# v001.net
KiCad netlist of a schematic drawn in EAGLE
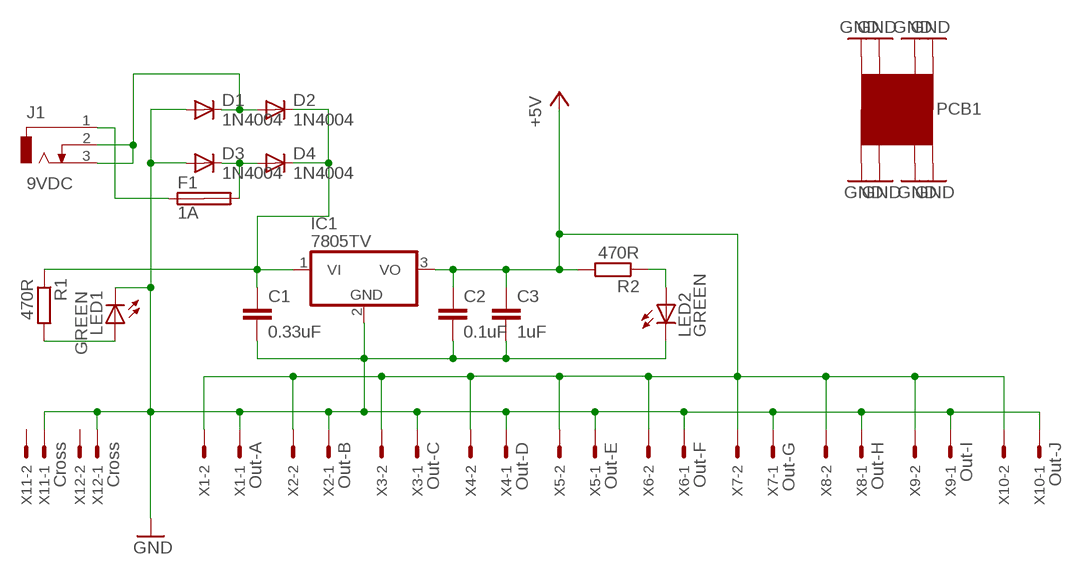
[diagram p0: schematic, sheet 1]

(export (version "E")
  (design (tool "Eeschema 10.0.6"))
  (components
    (comp (ref "C1")
      (value "0.33uF")
      (footprint "eagle-import:C050-030X075")
      (libsource (lib "eagle-import") (part "C-EU050-030X075"))
    )
    (comp (ref "C2")
      (value "0.1uF")
      (footprint "eagle-import:C050-024X044")
      (libsource (lib "eagle-import") (part "C-EU050-024X044"))
    )
    (comp (ref "C3")
      (value "1uF")
      (footprint "eagle-import:C050-045X075")
      (libsource (lib "eagle-import") (part "C-EU050-045X075"))
    )
    (comp (ref "D1")
      (value "1N4004")
      (footprint "eagle-import:DO35-7")
      (libsource (lib "eagle-import") (part "1N4148DO35-7"))
    )
    (comp (ref "D2")
      (value "1N4004")
      (footprint "eagle-import:DO35-7")
      (libsource (lib "eagle-import") (part "1N4148DO35-7"))
    )
    (comp (ref "D3")
      (value "1N4004")
      (footprint "eagle-import:DO35-7")
      (libsource (lib "eagle-import") (part "1N4148DO35-7"))
    )
    (comp (ref "D4")
      (value "1N4004")
      (footprint "eagle-import:DO35-7")
      (libsource (lib "eagle-import") (part "1N4148DO35-7"))
    )
    (comp (ref "F1")
      (value "1A")
      (footprint "eagle-import:SHK20L")
      (libsource (lib "eagle-import") (part "SHK20L"))
    )
    (comp (ref "IC1")
      (value "7805TV")
      (footprint "eagle-import:TO220V")
      (libsource (lib "eagle-import") (part "78TV05"))
    )
    (comp (ref "J1")
      (value "9VDC")
      (footprint "eagle-import:DCJ0202")
      (libsource (lib "eagle-import") (part "DCJ0202"))
    )
    (comp (ref "LED1")
      (value "GREEN")
      (footprint "eagle-import:LED3MM")
      (libsource (lib "eagle-import") (part "LED3MM"))
    )
    (comp (ref "LED2")
      (value "GREEN")
      (footprint "eagle-import:LED3MM")
      (libsource (lib "eagle-import") (part "LED3MM"))
    )
    (comp (ref "PCB1")
      (value "PCB05X05")
      (footprint "eagle-import:PCB_05X05")
      (libsource (lib "eagle-import") (part "PCB05X05"))
    )
    (comp (ref "R1")
      (value "470R")
      (footprint "eagle-import:0204_7")
      (libsource (lib "eagle-import") (part "R-EU_0204/7"))
    )
    (comp (ref "R2")
      (value "470R")
      (footprint "eagle-import:0204_7")
      (libsource (lib "eagle-import") (part "R-EU_0204/7"))
    )
    (comp (ref "X1")
      (value "Out-A")
      (footprint "eagle-import:6410-02")
      (libsource (lib "eagle-import") (part "22-?-0227-2021"))
    )
    (comp (ref "X2")
      (value "Out-B")
      (footprint "eagle-import:6410-02")
      (libsource (lib "eagle-import") (part "22-?-0227-2021"))
    )
    (comp (ref "X3")
      (value "Out-C")
      (footprint "eagle-import:6410-02")
      (libsource (lib "eagle-import") (part "22-?-0227-2021"))
    )
    (comp (ref "X4")
      (value "Out-D")
      (footprint "eagle-import:6410-02")
      (libsource (lib "eagle-import") (part "22-?-0227-2021"))
    )
    (comp (ref "X5")
      (value "Out-E")
      (footprint "eagle-import:6410-02")
      (libsource (lib "eagle-import") (part "22-?-0227-2021"))
    )
    (comp (ref "X6")
      (value "Out-F")
      (footprint "eagle-import:6410-02")
      (libsource (lib "eagle-import") (part "22-?-0227-2021"))
    )
    (comp (ref "X7")
      (value "Out-G")
      (footprint "eagle-import:6410-02")
      (libsource (lib "eagle-import") (part "22-?-0227-2021"))
    )
    (comp (ref "X8")
      (value "Out-H")
      (footprint "eagle-import:6410-02")
      (libsource (lib "eagle-import") (part "22-?-0227-2021"))
    )
    (comp (ref "X9")
      (value "Out-I")
      (footprint "eagle-import:6410-02")
      (libsource (lib "eagle-import") (part "22-?-0227-2021"))
    )
    (comp (ref "X10")
      (value "Out-J")
      (footprint "eagle-import:6410-02")
      (libsource (lib "eagle-import") (part "22-?-0227-2021"))
    )
    (comp (ref "X11")
      (value "Cross")
      (footprint "eagle-import:6410-02")
      (libsource (lib "eagle-import") (part "22-?-0227-2021"))
    )
    (comp (ref "X12")
      (value "Cross")
      (footprint "eagle-import:6410-02")
      (libsource (lib "eagle-import") (part "22-?-0227-2021"))
    )
  )
  (nets
    (net (code "1") (name "+5V") (class "Default")
      (node (ref "C2") (pin "1") (pinfunction "1_1") (pintype "passive"))
      (node (ref "C3") (pin "1") (pinfunction "1_1") (pintype "passive"))
      (node (ref "IC1") (pin "3") (pinfunction "VO_3") (pintype "passive"))
      (node (ref "R2") (pin "2") (pinfunction "2_2") (pintype "passive"))
      (node (ref "X1") (pin "2") (pinfunction "S_2") (pintype "passive"))
      (node (ref "X10") (pin "2") (pinfunction "S_2") (pintype "passive"))
      (node (ref "X2") (pin "2") (pinfunction "S_2") (pintype "passive"))
      (node (ref "X3") (pin "2") (pinfunction "S_2") (pintype "passive"))
      (node (ref "X4") (pin "2") (pinfunction "S_2") (pintype "passive"))
      (node (ref "X5") (pin "2") (pinfunction "S_2") (pintype "passive"))
      (node (ref "X6") (pin "2") (pinfunction "S_2") (pintype "passive"))
      (node (ref "X7") (pin "2") (pinfunction "S_2") (pintype "passive"))
      (node (ref "X8") (pin "2") (pinfunction "S_2") (pintype "passive"))
      (node (ref "X9") (pin "2") (pinfunction "S_2") (pintype "passive"))
    )
    (net (code "2") (name "GND") (class "Default")
      (node (ref "C1") (pin "2") (pinfunction "2_2") (pintype "passive"))
      (node (ref "C2") (pin "2") (pinfunction "2_2") (pintype "passive"))
      (node (ref "C3") (pin "2") (pinfunction "2_2") (pintype "passive"))
      (node (ref "D1") (pin "A") (pinfunction "A_A") (pintype "passive"))
      (node (ref "D3") (pin "A") (pinfunction "A_A") (pintype "passive"))
      (node (ref "IC1") (pin "2") (pinfunction "GND_2") (pintype "passive"))
      (node (ref "LED1") (pin "K") (pinfunction "C_K") (pintype "passive"))
      (node (ref "LED2") (pin "K") (pinfunction "C_K") (pintype "passive"))
      (node (ref "PCB1") (pin "GND@1") (pinfunction "GND_GND@1") (pintype "bidirectional"))
      (node (ref "PCB1") (pin "GND@2") (pinfunction "GND_GND@2") (pintype "bidirectional"))
      (node (ref "PCB1") (pin "GND@3") (pinfunction "GND_GND@3") (pintype "bidirectional"))
      (node (ref "PCB1") (pin "GND@4") (pinfunction "GND_GND@4") (pintype "bidirectional"))
      (node (ref "PCB1") (pin "GND@5") (pinfunction "GND_GND@5") (pintype "bidirectional"))
      (node (ref "PCB1") (pin "GND@6") (pinfunction "GND_GND@6") (pintype "bidirectional"))
      (node (ref "PCB1") (pin "GND@7") (pinfunction "GND_GND@7") (pintype "bidirectional"))
      (node (ref "PCB1") (pin "GND@8") (pinfunction "GND_GND@8") (pintype "bidirectional"))
      (node (ref "X1") (pin "1") (pinfunction "S_1") (pintype "passive"))
      (node (ref "X10") (pin "1") (pinfunction "S_1") (pintype "passive"))
      (node (ref "X11") (pin "1") (pinfunction "S_1") (pintype "passive"))
      (node (ref "X12") (pin "1") (pinfunction "S_1") (pintype "passive"))
      (node (ref "X2") (pin "1") (pinfunction "S_1") (pintype "passive"))
      (node (ref "X3") (pin "1") (pinfunction "S_1") (pintype "passive"))
      (node (ref "X4") (pin "1") (pinfunction "S_1") (pintype "passive"))
      (node (ref "X5") (pin "1") (pinfunction "S_1") (pintype "passive"))
      (node (ref "X6") (pin "1") (pinfunction "S_1") (pintype "passive"))
      (node (ref "X7") (pin "1") (pinfunction "S_1") (pintype "passive"))
      (node (ref "X8") (pin "1") (pinfunction "S_1") (pintype "passive"))
      (node (ref "X9") (pin "1") (pinfunction "S_1") (pintype "passive"))
    )
    (net (code "3") (name "Net-(D1-PadC)") (class "Default")
      (node (ref "D1") (pin "C") (pinfunction "C_C") (pintype "passive"))
      (node (ref "D2") (pin "A") (pinfunction "A_A") (pintype "passive"))
      (node (ref "J1") (pin "2") (pinfunction "2_2") (pintype "passive"))
      (node (ref "J1") (pin "3") (pinfunction "3_3") (pintype "passive"))
    )
    (net (code "4") (name "Net-(D3-PadC)") (class "Default")
      (node (ref "D3") (pin "C") (pinfunction "C_C") (pintype "passive"))
      (node (ref "D4") (pin "A") (pinfunction "A_A") (pintype "passive"))
      (node (ref "F1") (pin "2A") (pinfunction "2A_2A") (pintype "passive"))
    )
    (net (code "5") (name "Net-(F1-Pad1A)") (class "Default")
      (node (ref "F1") (pin "1A") (pinfunction "1A_1A") (pintype "passive"))
      (node (ref "J1") (pin "1") (pinfunction "1_1") (pintype "passive"))
    )
    (net (code "6") (name "Net-(IC1-VI)") (class "Default")
      (node (ref "C1") (pin "1") (pinfunction "1_1") (pintype "passive"))
      (node (ref "D2") (pin "C") (pinfunction "C_C") (pintype "passive"))
      (node (ref "D4") (pin "C") (pinfunction "C_C") (pintype "passive"))
      (node (ref "IC1") (pin "1") (pinfunction "VI_1") (pintype "input"))
      (node (ref "R1") (pin "1") (pinfunction "1_1") (pintype "passive"))
    )
    (net (code "7") (name "Net-(LED1-PadA)") (class "Default")
      (node (ref "LED1") (pin "A") (pinfunction "A_A") (pintype "passive"))
      (node (ref "R1") (pin "2") (pinfunction "2_2") (pintype "passive"))
    )
    (net (code "8") (name "Net-(LED2-PadA)") (class "Default")
      (node (ref "LED2") (pin "A") (pinfunction "A_A") (pintype "passive"))
      (node (ref "R2") (pin "1") (pinfunction "1_1") (pintype "passive"))
    )
    (net (code "9") (name "unconnected-(F1-Pad1B)") (class "Default")
      (node (ref "F1") (pin "1B") (pinfunction "1B_1B") (pintype "passive"))
    )
    (net (code "10") (name "unconnected-(F1-Pad2B)") (class "Default")
      (node (ref "F1") (pin "2B") (pinfunction "2B_2B") (pintype "passive"))
    )
    (net (code "11") (name "unconnected-(X11B-S-Pad2)") (class "Default")
      (node (ref "X11") (pin "2") (pinfunction "S_2") (pintype "passive"))
    )
    (net (code "12") (name "unconnected-(X12B-S-Pad2)") (class "Default")
      (node (ref "X12") (pin "2") (pinfunction "S_2") (pintype "passive"))
    )
  )
)
